# 2_PIS____BHC-A-2030-03____V1_0.net
KiCad netlist of a schematic drawn in Altium Designer
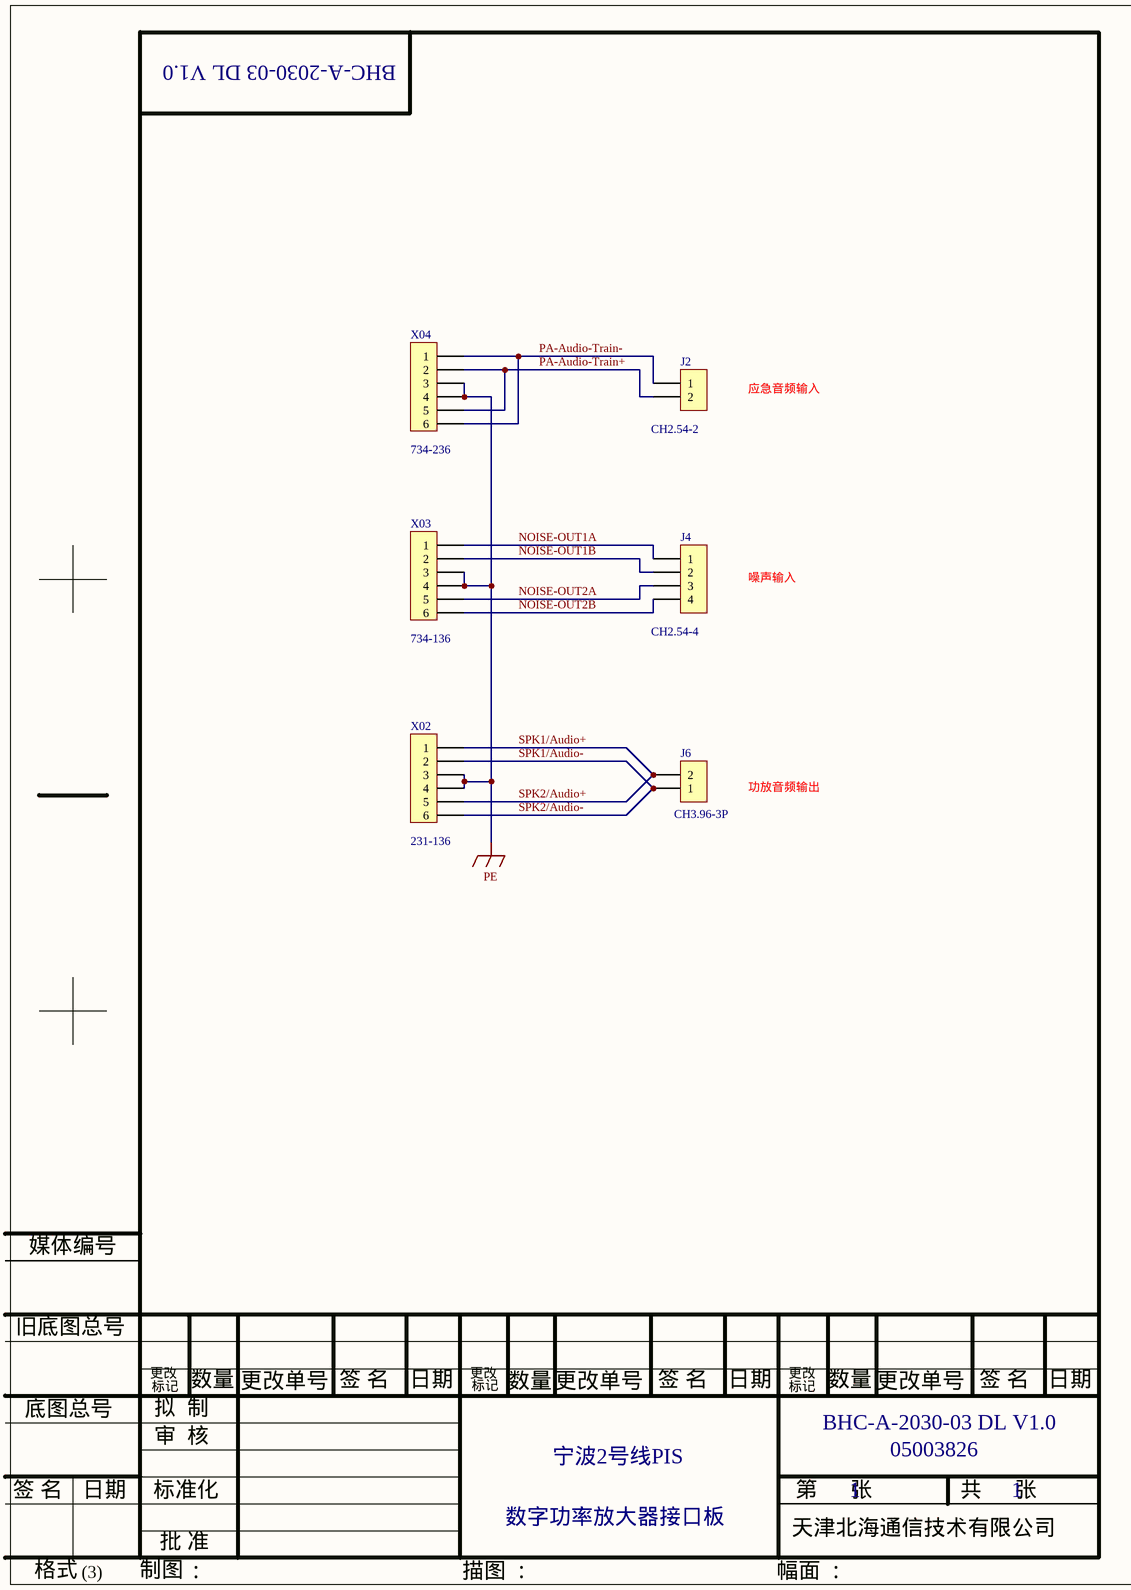
[diagram p0: 宁波2号线PIS_数字功率放大器_接口板(BHC-A-2030-03)_原理图_V1.0.SchDoc]

(export (version "E")
  (design (tool "Eeschema 10.0.6"))
  (components
    (comp (ref "J2")
      (value "CH2.54-2")
      (footprint "CH2.54-2")
      (description "Connector")
      (fields (field (name "Comment") "CON2"))
      (libsource (lib "SCH") (part "CON2"))
    )
    (comp (ref "J4")
      (value "CH2.54-4")
      (footprint "CH2.54-4")
      (fields (field (name "Comment") "CON4"))
      (libsource (lib "SCH") (part "CON4"))
    )
    (comp (ref "J6")
      (value "CH3.96-3P")
      (footprint "CH3.96-3P+")
      (description "Connector")
      (fields (field (name "Comment") "CON2"))
      (libsource (lib "") (part "CON2_1"))
    )
    (comp (ref "X02") (value "231-136") (footprint "wago-231-136") (libsource (lib "SCH") (part "CON6")))
    (comp (ref "X03") (value "734-136") (footprint "wago-734-136") (libsource (lib "SCH") (part "CON6")))
    (comp (ref "X04") (value "734-236") (footprint "WAGO-734-236") (libsource (lib "SCH") (part "CON6")))
  )
  (nets
    (net (code "1") (name "/NOISE-OUT1A") (class "Default")
      (node (ref "J4") (pin "1") (pinfunction "1_1") (pintype "passive"))
      (node (ref "X03") (pin "1") (pinfunction "1_1") (pintype "passive"))
    )
    (net (code "2") (name "/NOISE-OUT1B") (class "Default")
      (node (ref "J4") (pin "2") (pinfunction "2_2") (pintype "passive"))
      (node (ref "X03") (pin "2") (pinfunction "2_2") (pintype "passive"))
    )
    (net (code "3") (name "/NOISE-OUT2A") (class "Default")
      (node (ref "J4") (pin "3") (pinfunction "3_3") (pintype "passive"))
      (node (ref "X03") (pin "5") (pinfunction "5_5") (pintype "passive"))
    )
    (net (code "4") (name "/NOISE-OUT2B") (class "Default")
      (node (ref "J4") (pin "4") (pinfunction "4_4") (pintype "passive"))
      (node (ref "X03") (pin "6") (pinfunction "6_6") (pintype "passive"))
    )
    (net (code "5") (name "/PA-Audio-Train+") (class "Default")
      (node (ref "J2") (pin "2") (pinfunction "2_2") (pintype "passive"))
      (node (ref "X04") (pin "2") (pinfunction "2_2") (pintype "passive"))
      (node (ref "X04") (pin "5") (pinfunction "5_5") (pintype "passive"))
    )
    (net (code "6") (name "/PA-Audio-Train-") (class "Default")
      (node (ref "J2") (pin "1") (pinfunction "1_1") (pintype "passive"))
      (node (ref "X04") (pin "1") (pinfunction "1_1") (pintype "passive"))
      (node (ref "X04") (pin "6") (pinfunction "6_6") (pintype "passive"))
    )
    (net (code "7") (name "/SPK1{slash}Audio+") (class "Default")
      (node (ref "J6") (pin "2") (pinfunction "2_2") (pintype "passive"))
      (node (ref "X02") (pin "1") (pinfunction "1_1") (pintype "passive"))
      (node (ref "X02") (pin "5") (pinfunction "5_5") (pintype "passive"))
    )
    (net (code "8") (name "/SPK1{slash}Audio-") (class "Default")
      (node (ref "J6") (pin "1") (pinfunction "1_1") (pintype "passive"))
      (node (ref "X02") (pin "2") (pinfunction "2_2") (pintype "passive"))
      (node (ref "X02") (pin "6") (pinfunction "6_6") (pintype "passive"))
    )
    (net (code "9") (name "PE") (class "Default")
      (node (ref "X02") (pin "3") (pinfunction "3_3") (pintype "passive"))
      (node (ref "X02") (pin "4") (pinfunction "4_4") (pintype "passive"))
      (node (ref "X03") (pin "3") (pinfunction "3_3") (pintype "passive"))
      (node (ref "X03") (pin "4") (pinfunction "4_4") (pintype "passive"))
      (node (ref "X04") (pin "3") (pinfunction "3_3") (pintype "passive"))
      (node (ref "X04") (pin "4") (pinfunction "4_4") (pintype "passive"))
    )
  )
)
